# trace_8.net
KiCad netlist of a schematic drawn in Altium Designer
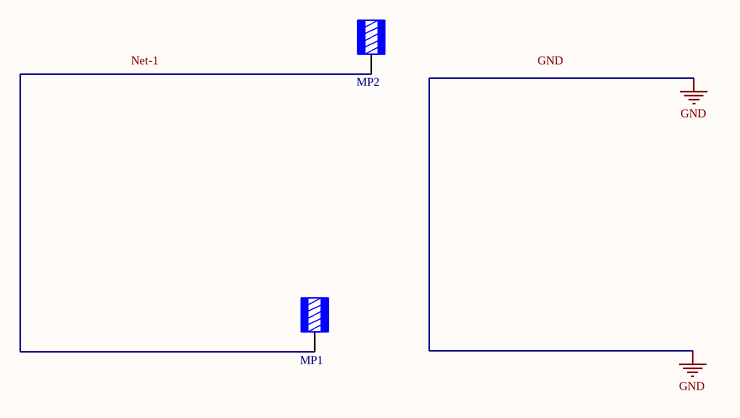
[diagram p0: trace_8.SchDoc]

(export (version "E")
  (design (tool "Eeschema 10.0.6"))
  (components
    (comp (ref "MP1")
      (value "74650074R")
      (footprint "WURTH 74650074")
      (description "TERM REDCUBE M4 4PIN PCB")
      (fields (field (name "MANUFACTURER") "Würth Elektronik"))
      (libsource (lib "Celestial Altium Library - altium_library") (part "MOUNTING POINT"))
    )
    (comp (ref "MP2")
      (value "74651194R")
      (footprint "WURTH 74651194")
      (description "TERM REDCUBE 9PIN PCB")
      (fields (field (name "MANUFACTURER") "Würth Elektronik"))
      (libsource (lib "Celestial Altium Library - altium_library") (part "MOUNTING POINT"))
    )
  )
  (nets
    (net (code "3") (name "Net-(MP1-Pad1)") (class "Default")
      (node (ref "MP1") (pin "1") (pinfunction "1_1") (pintype "passive"))
      (node (ref "MP2") (pin "1") (pinfunction "1_1") (pintype "passive"))
    )
  )
)
